# SCH_TrailCheaper_2024-05-27.net
KiCad netlist of a schematic drawn in EasyEDA
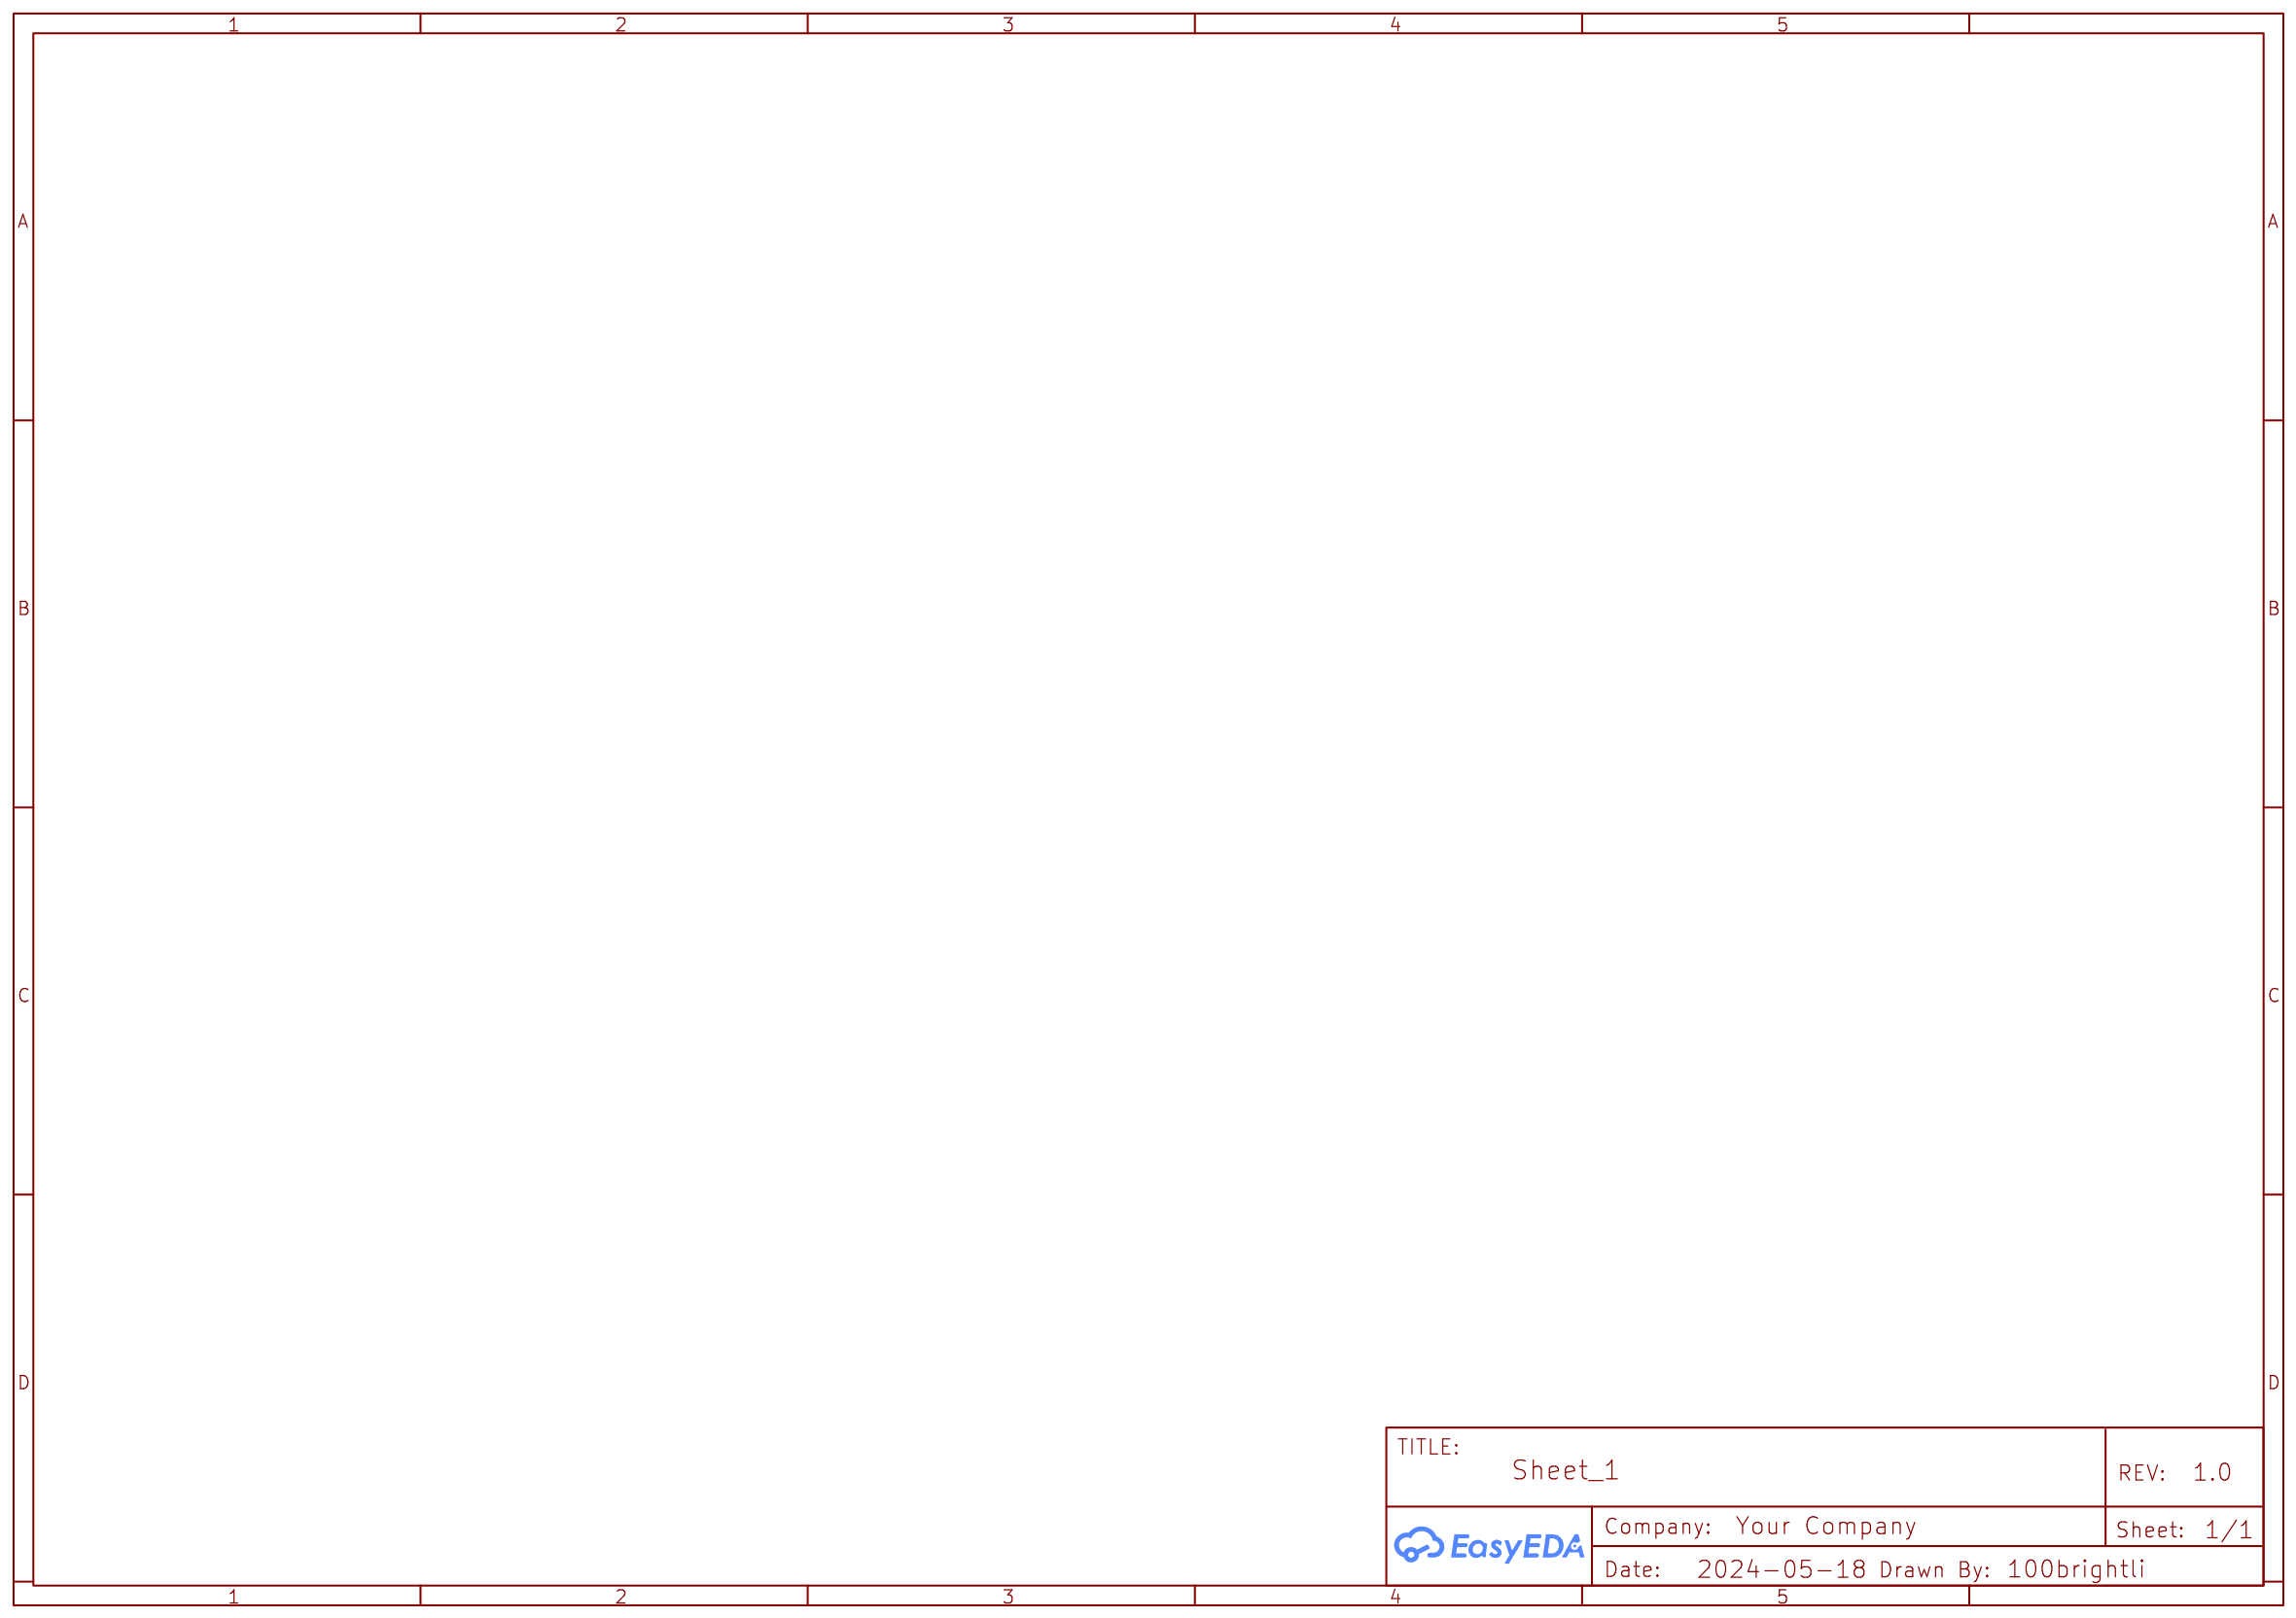
[diagram p0: Sheet_1]
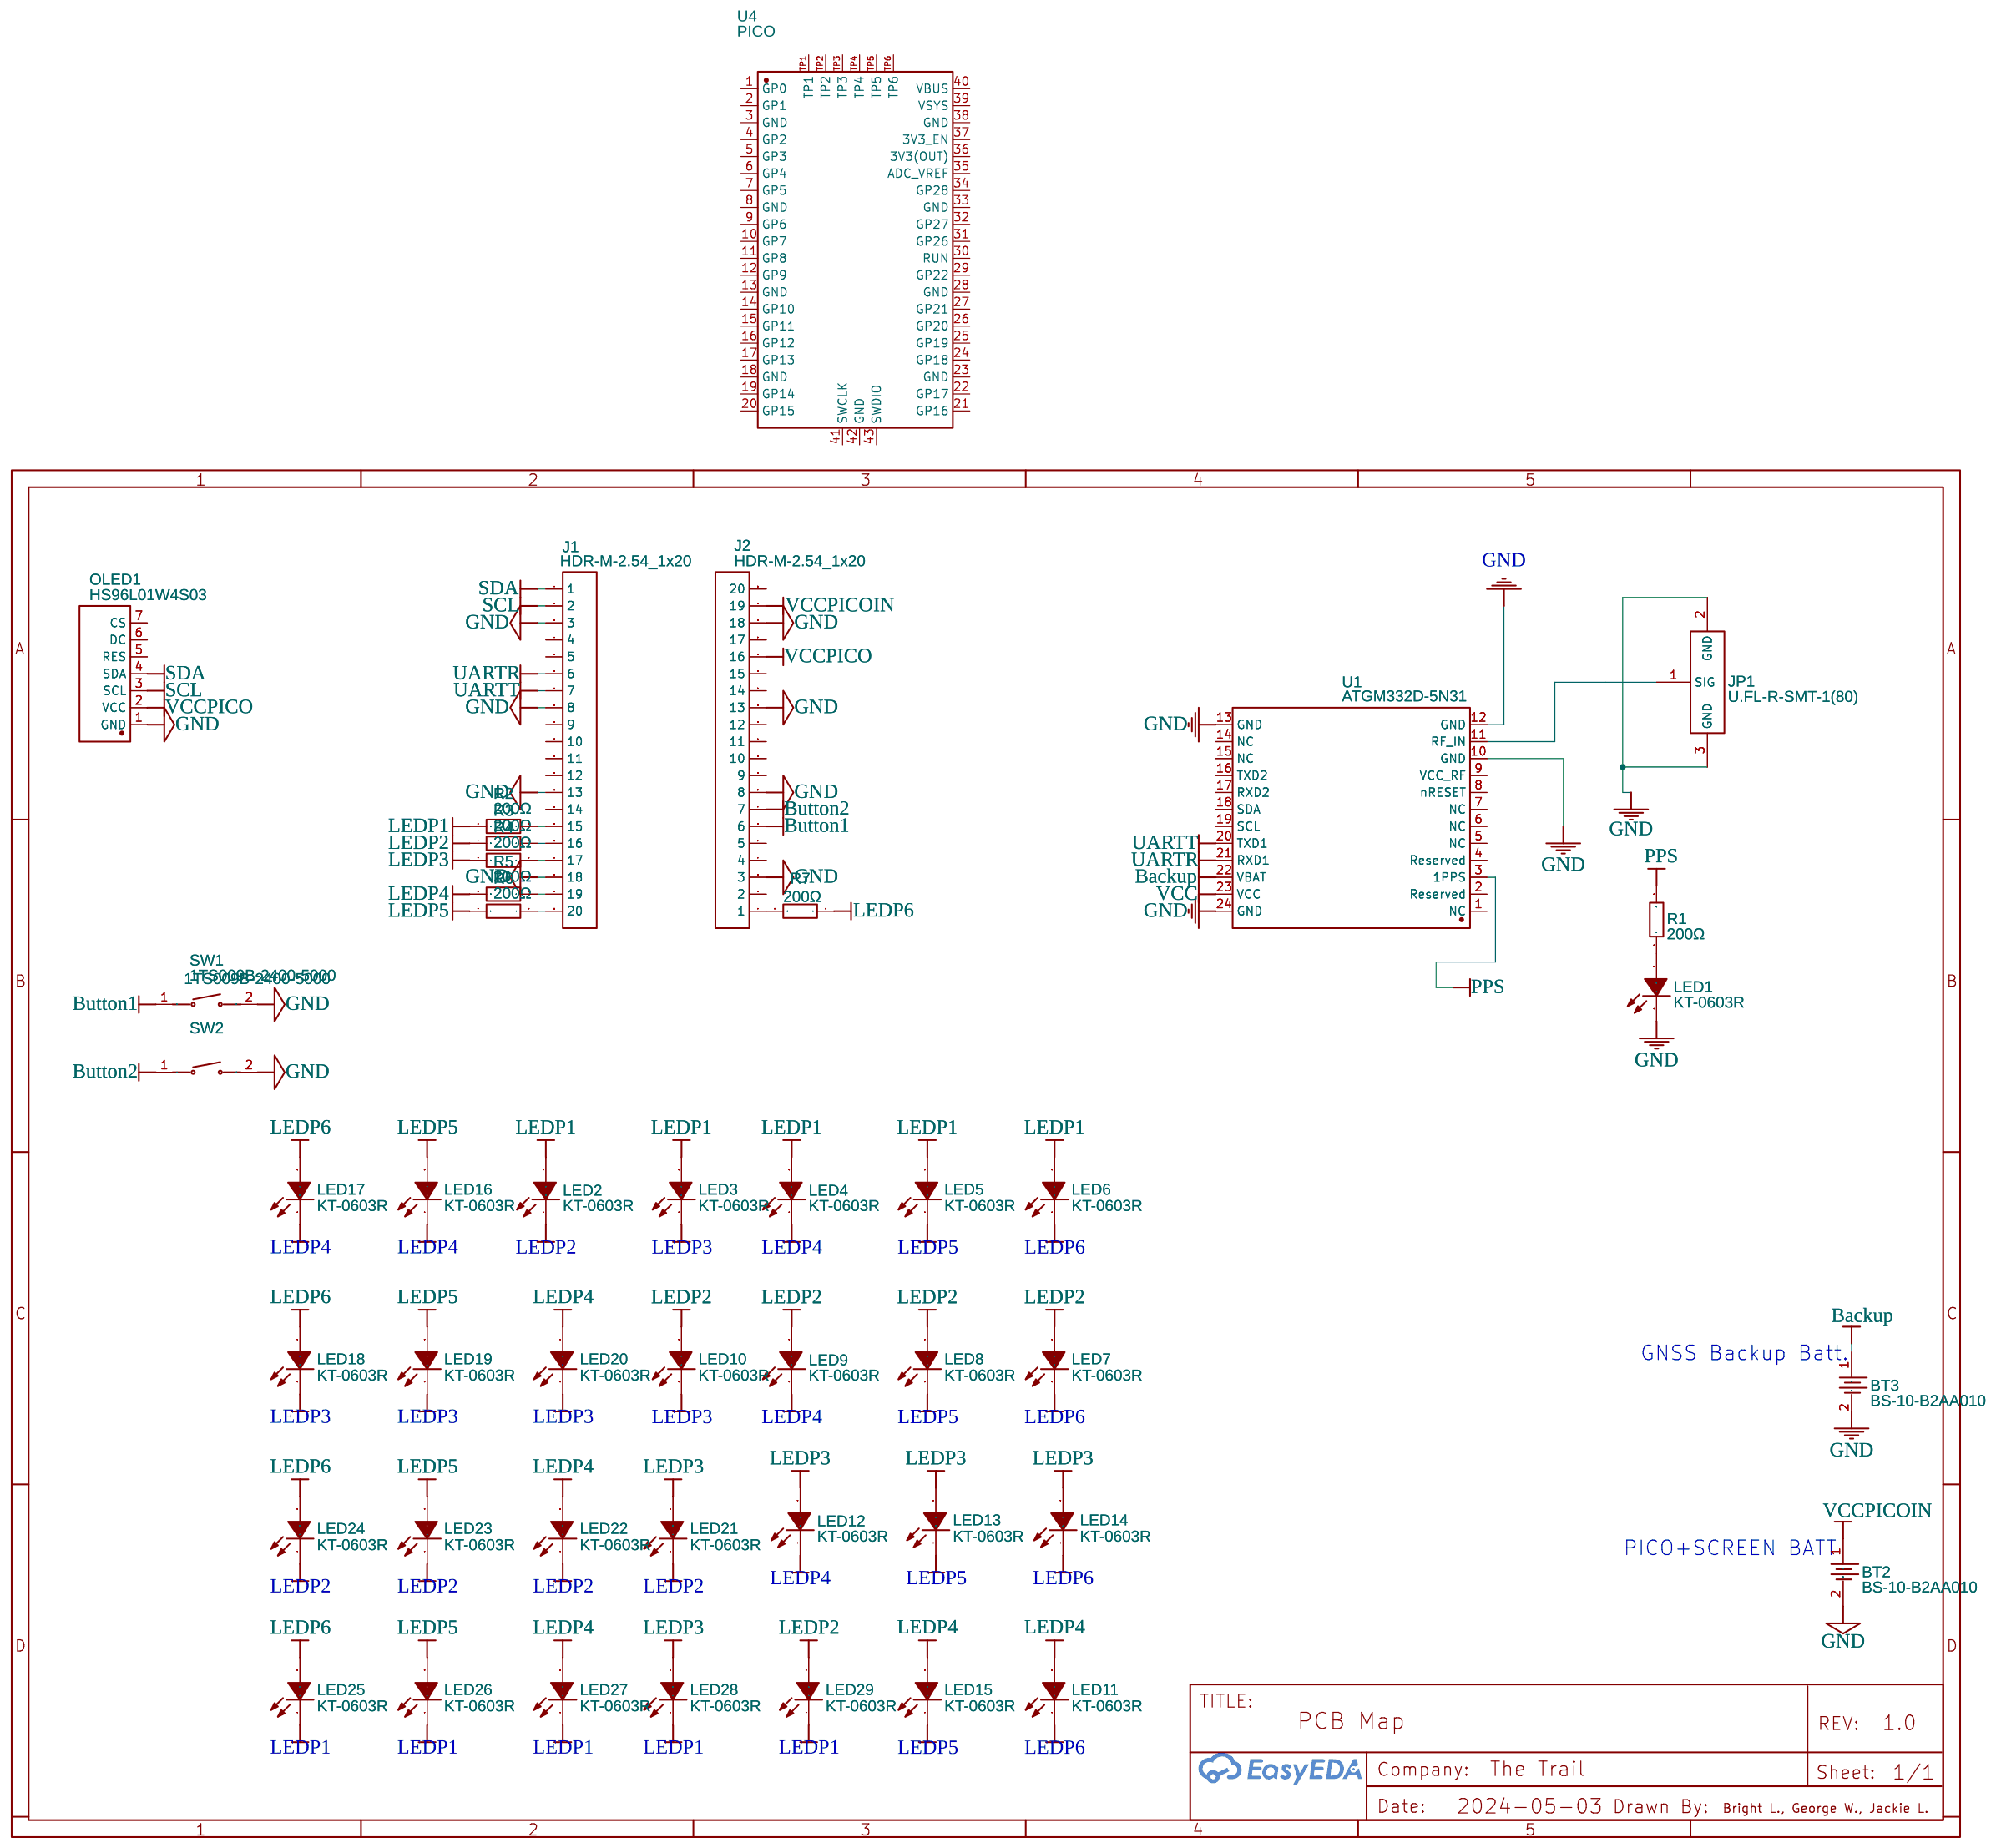
[diagram p1: Sheet_2_Cheaper? copy]

(export (version "E")
  (design (tool "Eeschema 10.0.6"))
  (components
    (comp (ref "BT2")
      (value "BS-10-B2AA010")
      (fields (field (name "Manufacturer") "MYOUNG(美阳)"))
      (libsource (lib "") (part "BS-10-B2AA010"))
    )
    (comp (ref "BT3")
      (value "BS-10-B2AA010")
      (fields (field (name "Manufacturer") "MYOUNG(美阳)"))
      (libsource (lib "") (part "BS-10-B2AA010"))
    )
    (comp (ref "J1") (value "HDR-M-2.54_1x20") (libsource (lib "") (part "HDR-M-2.54_1x20_1")))
    (comp (ref "J2") (value "HDR-M-2.54_1x20") (libsource (lib "") (part "HDR-M-2.54_1x20")))
    (comp (ref "JP1")
      (value "U.FL-R-SMT-1(80)")
      (fields (field (name "Manufacturer") "HRS(广濑)"))
      (libsource (lib "") (part "U.FL-R-SMT-1(80)"))
    )
    (comp (ref "LED1")
      (value "KT-0603R")
      (fields (field (name "Manufacturer") "KENTO"))
      (libsource (lib "") (part "KT-0603R"))
    )
    (comp (ref "LED2")
      (value "KT-0603R")
      (fields (field (name "Manufacturer") "KENTO"))
      (libsource (lib "") (part "KT-0603R"))
    )
    (comp (ref "LED3")
      (value "KT-0603R")
      (fields (field (name "Manufacturer") "KENTO"))
      (libsource (lib "") (part "KT-0603R"))
    )
    (comp (ref "LED4")
      (value "KT-0603R")
      (fields (field (name "Manufacturer") "KENTO"))
      (libsource (lib "") (part "KT-0603R"))
    )
    (comp (ref "LED5")
      (value "KT-0603R")
      (fields (field (name "Manufacturer") "KENTO"))
      (libsource (lib "") (part "KT-0603R"))
    )
    (comp (ref "LED6")
      (value "KT-0603R")
      (fields (field (name "Manufacturer") "KENTO"))
      (libsource (lib "") (part "KT-0603R"))
    )
    (comp (ref "LED7")
      (value "KT-0603R")
      (fields (field (name "Manufacturer") "KENTO"))
      (libsource (lib "") (part "KT-0603R"))
    )
    (comp (ref "LED8")
      (value "KT-0603R")
      (fields (field (name "Manufacturer") "KENTO"))
      (libsource (lib "") (part "KT-0603R"))
    )
    (comp (ref "LED9")
      (value "KT-0603R")
      (fields (field (name "Manufacturer") "KENTO"))
      (libsource (lib "") (part "KT-0603R"))
    )
    (comp (ref "LED10")
      (value "KT-0603R")
      (fields (field (name "Manufacturer") "KENTO"))
      (libsource (lib "") (part "KT-0603R"))
    )
    (comp (ref "LED11")
      (value "KT-0603R")
      (fields (field (name "Manufacturer") "KENTO"))
      (libsource (lib "") (part "KT-0603R"))
    )
    (comp (ref "LED12")
      (value "KT-0603R")
      (fields (field (name "Manufacturer") "KENTO"))
      (libsource (lib "") (part "KT-0603R"))
    )
    (comp (ref "LED13")
      (value "KT-0603R")
      (fields (field (name "Manufacturer") "KENTO"))
      (libsource (lib "") (part "KT-0603R"))
    )
    (comp (ref "LED14")
      (value "KT-0603R")
      (fields (field (name "Manufacturer") "KENTO"))
      (libsource (lib "") (part "KT-0603R"))
    )
    (comp (ref "LED15")
      (value "KT-0603R")
      (fields (field (name "Manufacturer") "KENTO"))
      (libsource (lib "") (part "KT-0603R"))
    )
    (comp (ref "LED16")
      (value "KT-0603R")
      (fields (field (name "Manufacturer") "KENTO"))
      (libsource (lib "") (part "KT-0603R"))
    )
    (comp (ref "LED17")
      (value "KT-0603R")
      (fields (field (name "Manufacturer") "KENTO"))
      (libsource (lib "") (part "KT-0603R"))
    )
    (comp (ref "LED18")
      (value "KT-0603R")
      (fields (field (name "Manufacturer") "KENTO"))
      (libsource (lib "") (part "KT-0603R"))
    )
    (comp (ref "LED19")
      (value "KT-0603R")
      (fields (field (name "Manufacturer") "KENTO"))
      (libsource (lib "") (part "KT-0603R"))
    )
    (comp (ref "LED20")
      (value "KT-0603R")
      (fields (field (name "Manufacturer") "KENTO"))
      (libsource (lib "") (part "KT-0603R"))
    )
    (comp (ref "LED21")
      (value "KT-0603R")
      (fields (field (name "Manufacturer") "KENTO"))
      (libsource (lib "") (part "KT-0603R"))
    )
    (comp (ref "LED22")
      (value "KT-0603R")
      (fields (field (name "Manufacturer") "KENTO"))
      (libsource (lib "") (part "KT-0603R"))
    )
    (comp (ref "LED23")
      (value "KT-0603R")
      (fields (field (name "Manufacturer") "KENTO"))
      (libsource (lib "") (part "KT-0603R"))
    )
    (comp (ref "LED24")
      (value "KT-0603R")
      (fields (field (name "Manufacturer") "KENTO"))
      (libsource (lib "") (part "KT-0603R"))
    )
    (comp (ref "LED25")
      (value "KT-0603R")
      (fields (field (name "Manufacturer") "KENTO"))
      (libsource (lib "") (part "KT-0603R"))
    )
    (comp (ref "LED26")
      (value "KT-0603R")
      (fields (field (name "Manufacturer") "KENTO"))
      (libsource (lib "") (part "KT-0603R"))
    )
    (comp (ref "LED27")
      (value "KT-0603R")
      (fields (field (name "Manufacturer") "KENTO"))
      (libsource (lib "") (part "KT-0603R"))
    )
    (comp (ref "LED28")
      (value "KT-0603R")
      (fields (field (name "Manufacturer") "KENTO"))
      (libsource (lib "") (part "KT-0603R"))
    )
    (comp (ref "LED29")
      (value "KT-0603R")
      (fields (field (name "Manufacturer") "KENTO"))
      (libsource (lib "") (part "KT-0603R"))
    )
    (comp (ref "OLED1")
      (value "HS96L01W4S03")
      (fields (field (name "Manufacturer") "HS(汉昇)"))
      (libsource (lib "") (part "HS96L01W4S03"))
    )
    (comp (ref "R1")
      (value "200Ω")
      (fields
        (field (name "Manufacturer Part") "0402WGF2000TCE")
        (field (name "Manufacturer") "UNI-ROYAL(厚声)")
      )
      (libsource (lib "") (part "0402WGF2000TCE_1"))
    )
    (comp (ref "R2")
      (value "200Ω")
      (fields
        (field (name "Manufacturer Part") "0402WGF2000TCE")
        (field (name "Manufacturer") "UNI-ROYAL(厚声)")
      )
      (libsource (lib "") (part "0402WGF2000TCE"))
    )
    (comp (ref "R3")
      (value "200Ω")
      (fields
        (field (name "Manufacturer Part") "0402WGF2000TCE")
        (field (name "Manufacturer") "UNI-ROYAL(厚声)")
      )
      (libsource (lib "") (part "0402WGF2000TCE"))
    )
    (comp (ref "R4")
      (value "200Ω")
      (fields
        (field (name "Manufacturer Part") "0402WGF2000TCE")
        (field (name "Manufacturer") "UNI-ROYAL(厚声)")
      )
      (libsource (lib "") (part "0402WGF2000TCE"))
    )
    (comp (ref "R5")
      (value "200Ω")
      (fields
        (field (name "Manufacturer Part") "0402WGF2000TCE")
        (field (name "Manufacturer") "UNI-ROYAL(厚声)")
      )
      (libsource (lib "") (part "0402WGF2000TCE"))
    )
    (comp (ref "R6")
      (value "200Ω")
      (fields
        (field (name "Manufacturer Part") "0402WGF2000TCE")
        (field (name "Manufacturer") "UNI-ROYAL(厚声)")
      )
      (libsource (lib "") (part "0402WGF2000TCE"))
    )
    (comp (ref "R7")
      (value "200Ω")
      (fields
        (field (name "Manufacturer Part") "0402WGF2000TCE")
        (field (name "Manufacturer") "UNI-ROYAL(厚声)")
      )
      (libsource (lib "") (part "0402WGF2000TCE"))
    )
    (comp (ref "SW1")
      (value "1TS009B-2400-5000")
      (fields
        (field (name "Manufacturer Part") "1TS009B-2400-5000-CT")
        (field (name "Manufacturer") "HYP(鸿源精密)")
      )
      (libsource (lib "") (part "1TS009B-2400-5000"))
    )
    (comp (ref "SW2")
      (value "1TS009B-2400-5000")
      (fields
        (field (name "Manufacturer Part") "1TS009B-2400-5000-CT")
        (field (name "Manufacturer") "HYP(鸿源精密)")
      )
      (libsource (lib "") (part "1TS009B-2400-5000"))
    )
    (comp (ref "U1")
      (value "ATGM332D-5N31")
      (fields (field (name "Manufacturer") "杭州中科微"))
      (libsource (lib "") (part "ATGM332D-5N31"))
    )
    (comp (ref "U4")
      (value "PICO")
      (fields (field (name "Manufacturer") "Raspberry Pi(树莓派)"))
      (libsource (lib "") (part "PICO"))
    )
  )
  (nets
    (net (code "1") (name "Backup") (class "Default")
      (node (ref "BT3") (pin "1") (pinfunction "1_1") (pintype "input"))
      (node (ref "U1") (pin "22") (pinfunction "VBAT_22") (pintype "unspecified"))
    )
    (net (code "2") (name "Button1") (class "Default")
      (node (ref "J2") (pin "6") (pinfunction "6_6") (pintype "unspecified"))
      (node (ref "SW1") (pin "1") (pinfunction "1_1") (pintype "unspecified"))
    )
    (net (code "3") (name "Button2") (class "Default")
      (node (ref "J2") (pin "7") (pinfunction "7_7") (pintype "unspecified"))
      (node (ref "SW2") (pin "1") (pinfunction "1_1") (pintype "unspecified"))
    )
    (net (code "4") (name "GND") (class "Default")
      (node (ref "BT2") (pin "2") (pinfunction "2_2") (pintype "input"))
      (node (ref "BT3") (pin "2") (pinfunction "2_2") (pintype "input"))
      (node (ref "J1") (pin "13") (pinfunction "13_13") (pintype "unspecified"))
      (node (ref "J1") (pin "18") (pinfunction "18_18") (pintype "unspecified"))
      (node (ref "J1") (pin "3") (pinfunction "3_3") (pintype "unspecified"))
      (node (ref "J1") (pin "8") (pinfunction "8_8") (pintype "unspecified"))
      (node (ref "J2") (pin "13") (pinfunction "13_13") (pintype "unspecified"))
      (node (ref "J2") (pin "18") (pinfunction "18_18") (pintype "unspecified"))
      (node (ref "J2") (pin "3") (pinfunction "3_3") (pintype "unspecified"))
      (node (ref "J2") (pin "8") (pinfunction "8_8") (pintype "unspecified"))
      (node (ref "JP1") (pin "2") (pinfunction "GND_2") (pintype "unspecified"))
      (node (ref "JP1") (pin "3") (pinfunction "GND_3") (pintype "unspecified"))
      (node (ref "LED1") (pin "1") (pinfunction "K_1") (pintype "unspecified"))
      (node (ref "OLED1") (pin "1") (pinfunction "GND_1") (pintype "unspecified"))
      (node (ref "SW1") (pin "2") (pinfunction "2_2") (pintype "unspecified"))
      (node (ref "SW2") (pin "2") (pinfunction "2_2") (pintype "unspecified"))
      (node (ref "U1") (pin "10") (pinfunction "GND_10") (pintype "unspecified"))
      (node (ref "U1") (pin "12") (pinfunction "GND_12") (pintype "unspecified"))
      (node (ref "U1") (pin "13") (pinfunction "GND_13") (pintype "unspecified"))
      (node (ref "U1") (pin "24") (pinfunction "GND_24") (pintype "unspecified"))
    )
    (net (code "5") (name "LEDP1") (class "Default")
      (node (ref "LED2") (pin "2") (pinfunction "A_2") (pintype "unspecified"))
      (node (ref "LED25") (pin "1") (pinfunction "K_1") (pintype "unspecified"))
      (node (ref "LED26") (pin "1") (pinfunction "K_1") (pintype "unspecified"))
      (node (ref "LED27") (pin "1") (pinfunction "K_1") (pintype "unspecified"))
      (node (ref "LED28") (pin "1") (pinfunction "K_1") (pintype "unspecified"))
      (node (ref "LED29") (pin "1") (pinfunction "K_1") (pintype "unspecified"))
      (node (ref "LED3") (pin "2") (pinfunction "A_2") (pintype "unspecified"))
      (node (ref "LED4") (pin "2") (pinfunction "A_2") (pintype "unspecified"))
      (node (ref "LED5") (pin "2") (pinfunction "A_2") (pintype "unspecified"))
      (node (ref "LED6") (pin "2") (pinfunction "A_2") (pintype "unspecified"))
      (node (ref "R2") (pin "2") (pinfunction "2_2") (pintype "input"))
    )
    (net (code "6") (name "LEDP2") (class "Default")
      (node (ref "LED10") (pin "2") (pinfunction "A_2") (pintype "unspecified"))
      (node (ref "LED2") (pin "1") (pinfunction "K_1") (pintype "unspecified"))
      (node (ref "LED21") (pin "1") (pinfunction "K_1") (pintype "unspecified"))
      (node (ref "LED22") (pin "1") (pinfunction "K_1") (pintype "unspecified"))
      (node (ref "LED23") (pin "1") (pinfunction "K_1") (pintype "unspecified"))
      (node (ref "LED24") (pin "1") (pinfunction "K_1") (pintype "unspecified"))
      (node (ref "LED29") (pin "2") (pinfunction "A_2") (pintype "unspecified"))
      (node (ref "LED7") (pin "2") (pinfunction "A_2") (pintype "unspecified"))
      (node (ref "LED8") (pin "2") (pinfunction "A_2") (pintype "unspecified"))
      (node (ref "LED9") (pin "2") (pinfunction "A_2") (pintype "unspecified"))
      (node (ref "R3") (pin "2") (pinfunction "2_2") (pintype "input"))
    )
    (net (code "7") (name "LEDP3") (class "Default")
      (node (ref "LED10") (pin "1") (pinfunction "K_1") (pintype "unspecified"))
      (node (ref "LED12") (pin "2") (pinfunction "A_2") (pintype "unspecified"))
      (node (ref "LED13") (pin "2") (pinfunction "A_2") (pintype "unspecified"))
      (node (ref "LED14") (pin "2") (pinfunction "A_2") (pintype "unspecified"))
      (node (ref "LED18") (pin "1") (pinfunction "K_1") (pintype "unspecified"))
      (node (ref "LED19") (pin "1") (pinfunction "K_1") (pintype "unspecified"))
      (node (ref "LED20") (pin "1") (pinfunction "K_1") (pintype "unspecified"))
      (node (ref "LED21") (pin "2") (pinfunction "A_2") (pintype "unspecified"))
      (node (ref "LED28") (pin "2") (pinfunction "A_2") (pintype "unspecified"))
      (node (ref "LED3") (pin "1") (pinfunction "K_1") (pintype "unspecified"))
      (node (ref "R4") (pin "2") (pinfunction "2_2") (pintype "input"))
    )
    (net (code "8") (name "LEDP4") (class "Default")
      (node (ref "LED11") (pin "2") (pinfunction "A_2") (pintype "unspecified"))
      (node (ref "LED12") (pin "1") (pinfunction "K_1") (pintype "unspecified"))
      (node (ref "LED15") (pin "2") (pinfunction "A_2") (pintype "unspecified"))
      (node (ref "LED16") (pin "1") (pinfunction "K_1") (pintype "unspecified"))
      (node (ref "LED17") (pin "1") (pinfunction "K_1") (pintype "unspecified"))
      (node (ref "LED20") (pin "2") (pinfunction "A_2") (pintype "unspecified"))
      (node (ref "LED22") (pin "2") (pinfunction "A_2") (pintype "unspecified"))
      (node (ref "LED27") (pin "2") (pinfunction "A_2") (pintype "unspecified"))
      (node (ref "LED4") (pin "1") (pinfunction "K_1") (pintype "unspecified"))
      (node (ref "LED9") (pin "1") (pinfunction "K_1") (pintype "unspecified"))
      (node (ref "R5") (pin "2") (pinfunction "2_2") (pintype "input"))
    )
    (net (code "9") (name "LEDP5") (class "Default")
      (node (ref "LED13") (pin "1") (pinfunction "K_1") (pintype "unspecified"))
      (node (ref "LED15") (pin "1") (pinfunction "K_1") (pintype "unspecified"))
      (node (ref "LED16") (pin "2") (pinfunction "A_2") (pintype "unspecified"))
      (node (ref "LED19") (pin "2") (pinfunction "A_2") (pintype "unspecified"))
      (node (ref "LED23") (pin "2") (pinfunction "A_2") (pintype "unspecified"))
      (node (ref "LED26") (pin "2") (pinfunction "A_2") (pintype "unspecified"))
      (node (ref "LED5") (pin "1") (pinfunction "K_1") (pintype "unspecified"))
      (node (ref "LED8") (pin "1") (pinfunction "K_1") (pintype "unspecified"))
      (node (ref "R6") (pin "2") (pinfunction "2_2") (pintype "input"))
    )
    (net (code "10") (name "LEDP6") (class "Default")
      (node (ref "LED11") (pin "1") (pinfunction "K_1") (pintype "unspecified"))
      (node (ref "LED14") (pin "1") (pinfunction "K_1") (pintype "unspecified"))
      (node (ref "LED17") (pin "2") (pinfunction "A_2") (pintype "unspecified"))
      (node (ref "LED18") (pin "2") (pinfunction "A_2") (pintype "unspecified"))
      (node (ref "LED24") (pin "2") (pinfunction "A_2") (pintype "unspecified"))
      (node (ref "LED25") (pin "2") (pinfunction "A_2") (pintype "unspecified"))
      (node (ref "LED6") (pin "1") (pinfunction "K_1") (pintype "unspecified"))
      (node (ref "LED7") (pin "1") (pinfunction "K_1") (pintype "unspecified"))
      (node (ref "R7") (pin "1") (pinfunction "1_1") (pintype "input"))
    )
    (net (code "11") (name "Net-(J1-Pad15)") (class "Default")
      (node (ref "J1") (pin "15") (pinfunction "15_15") (pintype "unspecified"))
      (node (ref "R2") (pin "1") (pinfunction "1_1") (pintype "input"))
    )
    (net (code "12") (name "Net-(J1-Pad16)") (class "Default")
      (node (ref "J1") (pin "16") (pinfunction "16_16") (pintype "unspecified"))
      (node (ref "R3") (pin "1") (pinfunction "1_1") (pintype "input"))
    )
    (net (code "13") (name "Net-(J1-Pad17)") (class "Default")
      (node (ref "J1") (pin "17") (pinfunction "17_17") (pintype "unspecified"))
      (node (ref "R4") (pin "1") (pinfunction "1_1") (pintype "input"))
    )
    (net (code "14") (name "Net-(J1-Pad19)") (class "Default")
      (node (ref "J1") (pin "19") (pinfunction "19_19") (pintype "unspecified"))
      (node (ref "R5") (pin "1") (pinfunction "1_1") (pintype "input"))
    )
    (net (code "15") (name "Net-(J1-Pad20)") (class "Default")
      (node (ref "J1") (pin "20") (pinfunction "20_20") (pintype "unspecified"))
      (node (ref "R6") (pin "1") (pinfunction "1_1") (pintype "input"))
    )
    (net (code "16") (name "Net-(J2-Pad1)") (class "Default")
      (node (ref "J2") (pin "1") (pinfunction "1_1") (pintype "unspecified"))
      (node (ref "R7") (pin "2") (pinfunction "2_2") (pintype "input"))
    )
    (net (code "17") (name "Net-(JP1-SIG)") (class "Default")
      (node (ref "JP1") (pin "1") (pinfunction "SIG_1") (pintype "unspecified"))
      (node (ref "U1") (pin "11") (pinfunction "RF_IN_11") (pintype "unspecified"))
    )
    (net (code "18") (name "Net-(LED1-A)") (class "Default")
      (node (ref "LED1") (pin "2") (pinfunction "A_2") (pintype "unspecified"))
      (node (ref "R1") (pin "1") (pinfunction "1_1") (pintype "input"))
    )
    (net (code "19") (name "PPS") (class "Default")
      (node (ref "R1") (pin "2") (pinfunction "2_2") (pintype "input"))
      (node (ref "U1") (pin "3") (pinfunction "1PPS_3") (pintype "unspecified"))
    )
    (net (code "20") (name "SCL") (class "Default")
      (node (ref "J1") (pin "2") (pinfunction "2_2") (pintype "unspecified"))
      (node (ref "OLED1") (pin "3") (pinfunction "SCL_3") (pintype "unspecified"))
    )
    (net (code "21") (name "SDA") (class "Default")
      (node (ref "J1") (pin "1") (pinfunction "1_1") (pintype "unspecified"))
      (node (ref "OLED1") (pin "4") (pinfunction "SDA_4") (pintype "unspecified"))
    )
    (net (code "22") (name "UARTR") (class "Default")
      (node (ref "J1") (pin "6") (pinfunction "6_6") (pintype "unspecified"))
      (node (ref "U1") (pin "21") (pinfunction "RXD1_21") (pintype "unspecified"))
    )
    (net (code "23") (name "UARTT") (class "Default")
      (node (ref "J1") (pin "7") (pinfunction "7_7") (pintype "unspecified"))
      (node (ref "U1") (pin "20") (pinfunction "TXD1_20") (pintype "unspecified"))
    )
    (net (code "24") (name "VCC") (class "Default")
      (node (ref "U1") (pin "23") (pinfunction "VCC_23") (pintype "unspecified"))
    )
    (net (code "25") (name "VCCPICO") (class "Default")
      (node (ref "J2") (pin "16") (pinfunction "16_16") (pintype "unspecified"))
      (node (ref "OLED1") (pin "2") (pinfunction "VCC_2") (pintype "unspecified"))
    )
    (net (code "26") (name "VCCPICOIN") (class "Default")
      (node (ref "BT2") (pin "1") (pinfunction "1_1") (pintype "input"))
      (node (ref "J2") (pin "19") (pinfunction "19_19") (pintype "unspecified"))
    )
    (net (code "27") (name "unconnected-(J1-Pad4)") (class "Default")
      (node (ref "J1") (pin "4") (pinfunction "4_4") (pintype "unspecified"))
    )
    (net (code "28") (name "unconnected-(J1-Pad5)") (class "Default")
      (node (ref "J1") (pin "5") (pinfunction "5_5") (pintype "unspecified"))
    )
    (net (code "29") (name "unconnected-(J1-Pad9)") (class "Default")
      (node (ref "J1") (pin "9") (pinfunction "9_9") (pintype "unspecified"))
    )
    (net (code "30") (name "unconnected-(J1-Pad10)") (class "Default")
      (node (ref "J1") (pin "10") (pinfunction "10_10") (pintype "unspecified"))
    )
    (net (code "31") (name "unconnected-(J1-Pad11)") (class "Default")
      (node (ref "J1") (pin "11") (pinfunction "11_11") (pintype "unspecified"))
    )
    (net (code "32") (name "unconnected-(J1-Pad12)") (class "Default")
      (node (ref "J1") (pin "12") (pinfunction "12_12") (pintype "unspecified"))
    )
    (net (code "33") (name "unconnected-(J1-Pad14)") (class "Default")
      (node (ref "J1") (pin "14") (pinfunction "14_14") (pintype "unspecified"))
    )
    (net (code "34") (name "unconnected-(J2-Pad2)") (class "Default")
      (node (ref "J2") (pin "2") (pinfunction "2_2") (pintype "unspecified"))
    )
    (net (code "35") (name "unconnected-(J2-Pad4)") (class "Default")
      (node (ref "J2") (pin "4") (pinfunction "4_4") (pintype "unspecified"))
    )
    (net (code "36") (name "unconnected-(J2-Pad5)") (class "Default")
      (node (ref "J2") (pin "5") (pinfunction "5_5") (pintype "unspecified"))
    )
    (net (code "37") (name "unconnected-(J2-Pad9)") (class "Default")
      (node (ref "J2") (pin "9") (pinfunction "9_9") (pintype "unspecified"))
    )
    (net (code "38") (name "unconnected-(J2-Pad10)") (class "Default")
      (node (ref "J2") (pin "10") (pinfunction "10_10") (pintype "unspecified"))
    )
    (net (code "39") (name "unconnected-(J2-Pad11)") (class "Default")
      (node (ref "J2") (pin "11") (pinfunction "11_11") (pintype "unspecified"))
    )
    (net (code "40") (name "unconnected-(J2-Pad12)") (class "Default")
      (node (ref "J2") (pin "12") (pinfunction "12_12") (pintype "unspecified"))
    )
    (net (code "41") (name "unconnected-(J2-Pad14)") (class "Default")
      (node (ref "J2") (pin "14") (pinfunction "14_14") (pintype "unspecified"))
    )
    (net (code "42") (name "unconnected-(J2-Pad15)") (class "Default")
      (node (ref "J2") (pin "15") (pinfunction "15_15") (pintype "unspecified"))
    )
    (net (code "43") (name "unconnected-(J2-Pad17)") (class "Default")
      (node (ref "J2") (pin "17") (pinfunction "17_17") (pintype "unspecified"))
    )
    (net (code "44") (name "unconnected-(J2-Pad20)") (class "Default")
      (node (ref "J2") (pin "20") (pinfunction "20_20") (pintype "unspecified"))
    )
    (net (code "45") (name "unconnected-(OLED1-CS-Pad7)") (class "Default")
      (node (ref "OLED1") (pin "7") (pinfunction "CS_7") (pintype "unspecified"))
    )
    (net (code "46") (name "unconnected-(OLED1-DC-Pad6)") (class "Default")
      (node (ref "OLED1") (pin "6") (pinfunction "DC_6") (pintype "unspecified"))
    )
    (net (code "47") (name "unconnected-(OLED1-RES-Pad5)") (class "Default")
      (node (ref "OLED1") (pin "5") (pinfunction "RES_5") (pintype "unspecified"))
    )
    (net (code "48") (name "unconnected-(U1-NC-Pad1)") (class "Default")
      (node (ref "U1") (pin "1") (pinfunction "NC_1") (pintype "unspecified"))
    )
    (net (code "49") (name "unconnected-(U1-NC-Pad5)") (class "Default")
      (node (ref "U1") (pin "5") (pinfunction "NC_5") (pintype "unspecified"))
    )
    (net (code "50") (name "unconnected-(U1-NC-Pad6)") (class "Default")
      (node (ref "U1") (pin "6") (pinfunction "NC_6") (pintype "unspecified"))
    )
    (net (code "51") (name "unconnected-(U1-NC-Pad7)") (class "Default")
      (node (ref "U1") (pin "7") (pinfunction "NC_7") (pintype "unspecified"))
    )
    (net (code "52") (name "unconnected-(U1-NC-Pad14)") (class "Default")
      (node (ref "U1") (pin "14") (pinfunction "NC_14") (pintype "unspecified"))
    )
    (net (code "53") (name "unconnected-(U1-NC-Pad15)") (class "Default")
      (node (ref "U1") (pin "15") (pinfunction "NC_15") (pintype "unspecified"))
    )
    (net (code "54") (name "unconnected-(U1-RXD2-Pad17)") (class "Default")
      (node (ref "U1") (pin "17") (pinfunction "RXD2_17") (pintype "unspecified"))
    )
    (net (code "55") (name "unconnected-(U1-Reserved-Pad2)") (class "Default")
      (node (ref "U1") (pin "2") (pinfunction "Reserved_2") (pintype "unspecified"))
    )
    (net (code "56") (name "unconnected-(U1-Reserved-Pad4)") (class "Default")
      (node (ref "U1") (pin "4") (pinfunction "Reserved_4") (pintype "unspecified"))
    )
    (net (code "57") (name "unconnected-(U1-SCL-Pad19)") (class "Default")
      (node (ref "U1") (pin "19") (pinfunction "SCL_19") (pintype "unspecified"))
    )
    (net (code "58") (name "unconnected-(U1-SDA-Pad18)") (class "Default")
      (node (ref "U1") (pin "18") (pinfunction "SDA_18") (pintype "unspecified"))
    )
    (net (code "59") (name "unconnected-(U1-TXD2-Pad16)") (class "Default")
      (node (ref "U1") (pin "16") (pinfunction "TXD2_16") (pintype "unspecified"))
    )
    (net (code "60") (name "unconnected-(U1-VCC_RF-Pad9)") (class "Default")
      (node (ref "U1") (pin "9") (pinfunction "VCC_RF_9") (pintype "unspecified"))
    )
    (net (code "61") (name "unconnected-(U1-nRESET-Pad8)") (class "Default")
      (node (ref "U1") (pin "8") (pinfunction "nRESET_8") (pintype "unspecified"))
    )
    (net (code "62") (name "unconnected-(U4-3V3(OUT)-Pad36)") (class "Default")
      (node (ref "U4") (pin "36") (pinfunction "3V3(OUT)_36") (pintype "unspecified"))
    )
    (net (code "63") (name "unconnected-(U4-3V3_EN-Pad37)") (class "Default")
      (node (ref "U4") (pin "37") (pinfunction "3V3_EN_37") (pintype "unspecified"))
    )
    (net (code "64") (name "unconnected-(U4-ADC_VREF-Pad35)") (class "Default")
      (node (ref "U4") (pin "35") (pinfunction "ADC_VREF_35") (pintype "unspecified"))
    )
    (net (code "65") (name "unconnected-(U4-GND-Pad3)") (class "Default")
      (node (ref "U4") (pin "3") (pinfunction "GND_3") (pintype "unspecified"))
    )
    (net (code "66") (name "unconnected-(U4-GND-Pad8)") (class "Default")
      (node (ref "U4") (pin "8") (pinfunction "GND_8") (pintype "unspecified"))
    )
    (net (code "67") (name "unconnected-(U4-GND-Pad13)") (class "Default")
      (node (ref "U4") (pin "13") (pinfunction "GND_13") (pintype "unspecified"))
    )
    (net (code "68") (name "unconnected-(U4-GND-Pad18)") (class "Default")
      (node (ref "U4") (pin "18") (pinfunction "GND_18") (pintype "unspecified"))
    )
    (net (code "69") (name "unconnected-(U4-GND-Pad23)") (class "Default")
      (node (ref "U4") (pin "23") (pinfunction "GND_23") (pintype "unspecified"))
    )
    (net (code "70") (name "unconnected-(U4-GND-Pad28)") (class "Default")
      (node (ref "U4") (pin "28") (pinfunction "GND_28") (pintype "unspecified"))
    )
    (net (code "71") (name "unconnected-(U4-GND-Pad33)") (class "Default")
      (node (ref "U4") (pin "33") (pinfunction "GND_33") (pintype "unspecified"))
    )
    (net (code "72") (name "unconnected-(U4-GND-Pad38)") (class "Default")
      (node (ref "U4") (pin "38") (pinfunction "GND_38") (pintype "unspecified"))
    )
    (net (code "73") (name "unconnected-(U4-GND-Pad42)") (class "Default")
      (node (ref "U4") (pin "42") (pinfunction "GND_42") (pintype "unspecified"))
    )
    (net (code "74") (name "unconnected-(U4-GP0-Pad1)") (class "Default")
      (node (ref "U4") (pin "1") (pinfunction "GP0_1") (pintype "unspecified"))
    )
    (net (code "75") (name "unconnected-(U4-GP1-Pad2)") (class "Default")
      (node (ref "U4") (pin "2") (pinfunction "GP1_2") (pintype "unspecified"))
    )
    (net (code "76") (name "unconnected-(U4-GP2-Pad4)") (class "Default")
      (node (ref "U4") (pin "4") (pinfunction "GP2_4") (pintype "unspecified"))
    )
    (net (code "77") (name "unconnected-(U4-GP3-Pad5)") (class "Default")
      (node (ref "U4") (pin "5") (pinfunction "GP3_5") (pintype "unspecified"))
    )
    (net (code "78") (name "unconnected-(U4-GP4-Pad6)") (class "Default")
      (node (ref "U4") (pin "6") (pinfunction "GP4_6") (pintype "unspecified"))
    )
    (net (code "79") (name "unconnected-(U4-GP5-Pad7)") (class "Default")
      (node (ref "U4") (pin "7") (pinfunction "GP5_7") (pintype "unspecified"))
    )
    (net (code "80") (name "unconnected-(U4-GP6-Pad9)") (class "Default")
      (node (ref "U4") (pin "9") (pinfunction "GP6_9") (pintype "unspecified"))
    )
    (net (code "81") (name "unconnected-(U4-GP7-Pad10)") (class "Default")
      (node (ref "U4") (pin "10") (pinfunction "GP7_10") (pintype "unspecified"))
    )
    (net (code "82") (name "unconnected-(U4-GP8-Pad11)") (class "Default")
      (node (ref "U4") (pin "11") (pinfunction "GP8_11") (pintype "unspecified"))
    )
    (net (code "83") (name "unconnected-(U4-GP9-Pad12)") (class "Default")
      (node (ref "U4") (pin "12") (pinfunction "GP9_12") (pintype "unspecified"))
    )
    (net (code "84") (name "unconnected-(U4-GP10-Pad14)") (class "Default")
      (node (ref "U4") (pin "14") (pinfunction "GP10_14") (pintype "unspecified"))
    )
    (net (code "85") (name "unconnected-(U4-GP11-Pad15)") (class "Default")
      (node (ref "U4") (pin "15") (pinfunction "GP11_15") (pintype "unspecified"))
    )
    (net (code "86") (name "unconnected-(U4-GP12-Pad16)") (class "Default")
      (node (ref "U4") (pin "16") (pinfunction "GP12_16") (pintype "unspecified"))
    )
    (net (code "87") (name "unconnected-(U4-GP13-Pad17)") (class "Default")
      (node (ref "U4") (pin "17") (pinfunction "GP13_17") (pintype "unspecified"))
    )
    (net (code "88") (name "unconnected-(U4-GP14-Pad19)") (class "Default")
      (node (ref "U4") (pin "19") (pinfunction "GP14_19") (pintype "unspecified"))
    )
    (net (code "89") (name "unconnected-(U4-GP15-Pad20)") (class "Default")
      (node (ref "U4") (pin "20") (pinfunction "GP15_20") (pintype "unspecified"))
    )
    (net (code "90") (name "unconnected-(U4-GP16-Pad21)") (class "Default")
      (node (ref "U4") (pin "21") (pinfunction "GP16_21") (pintype "unspecified"))
    )
    (net (code "91") (name "unconnected-(U4-GP17-Pad22)") (class "Default")
      (node (ref "U4") (pin "22") (pinfunction "GP17_22") (pintype "unspecified"))
    )
    (net (code "92") (name "unconnected-(U4-GP18-Pad24)") (class "Default")
      (node (ref "U4") (pin "24") (pinfunction "GP18_24") (pintype "unspecified"))
    )
    (net (code "93") (name "unconnected-(U4-GP19-Pad25)") (class "Default")
      (node (ref "U4") (pin "25") (pinfunction "GP19_25") (pintype "unspecified"))
    )
    (net (code "94") (name "unconnected-(U4-GP20-Pad26)") (class "Default")
      (node (ref "U4") (pin "26") (pinfunction "GP20_26") (pintype "unspecified"))
    )
    (net (code "95") (name "unconnected-(U4-GP21-Pad27)") (class "Default")
      (node (ref "U4") (pin "27") (pinfunction "GP21_27") (pintype "unspecified"))
    )
    (net (code "96") (name "unconnected-(U4-GP22-Pad29)") (class "Default")
      (node (ref "U4") (pin "29") (pinfunction "GP22_29") (pintype "unspecified"))
    )
    (net (code "97") (name "unconnected-(U4-GP26-Pad31)") (class "Default")
      (node (ref "U4") (pin "31") (pinfunction "GP26_31") (pintype "unspecified"))
    )
    (net (code "98") (name "unconnected-(U4-GP27-Pad32)") (class "Default")
      (node (ref "U4") (pin "32") (pinfunction "GP27_32") (pintype "unspecified"))
    )
    (net (code "99") (name "unconnected-(U4-GP28-Pad34)") (class "Default")
      (node (ref "U4") (pin "34") (pinfunction "GP28_34") (pintype "unspecified"))
    )
    (net (code "100") (name "unconnected-(U4-PadTP1)") (class "Default")
      (node (ref "U4") (pin "TP1") (pinfunction "TP1_TP1") (pintype "unspecified"))
    )
    (net (code "101") (name "unconnected-(U4-PadTP2)") (class "Default")
      (node (ref "U4") (pin "TP2") (pinfunction "TP2_TP2") (pintype "unspecified"))
    )
    (net (code "102") (name "unconnected-(U4-PadTP3)") (class "Default")
      (node (ref "U4") (pin "TP3") (pinfunction "TP3_TP3") (pintype "unspecified"))
    )
    (net (code "103") (name "unconnected-(U4-PadTP4)") (class "Default")
      (node (ref "U4") (pin "TP4") (pinfunction "TP4_TP4") (pintype "unspecified"))
    )
    (net (code "104") (name "unconnected-(U4-PadTP5)") (class "Default")
      (node (ref "U4") (pin "TP5") (pinfunction "TP5_TP5") (pintype "unspecified"))
    )
    (net (code "105") (name "unconnected-(U4-PadTP6)") (class "Default")
      (node (ref "U4") (pin "TP6") (pinfunction "TP6_TP6") (pintype "unspecified"))
    )
    (net (code "106") (name "unconnected-(U4-RUN-Pad30)") (class "Default")
      (node (ref "U4") (pin "30") (pinfunction "RUN_30") (pintype "unspecified"))
    )
    (net (code "107") (name "unconnected-(U4-SWCLK-Pad41)") (class "Default")
      (node (ref "U4") (pin "41") (pinfunction "SWCLK_41") (pintype "unspecified"))
    )
    (net (code "108") (name "unconnected-(U4-SWDIO-Pad43)") (class "Default")
      (node (ref "U4") (pin "43") (pinfunction "SWDIO_43") (pintype "unspecified"))
    )
    (net (code "109") (name "unconnected-(U4-VBUS-Pad40)") (class "Default")
      (node (ref "U4") (pin "40") (pinfunction "VBUS_40") (pintype "unspecified"))
    )
    (net (code "110") (name "unconnected-(U4-VSYS-Pad39)") (class "Default")
      (node (ref "U4") (pin "39") (pinfunction "VSYS_39") (pintype "unspecified"))
    )
  )
)
